# radiationsensor_r1.net
KiCad netlist of a schematic drawn in EAGLE
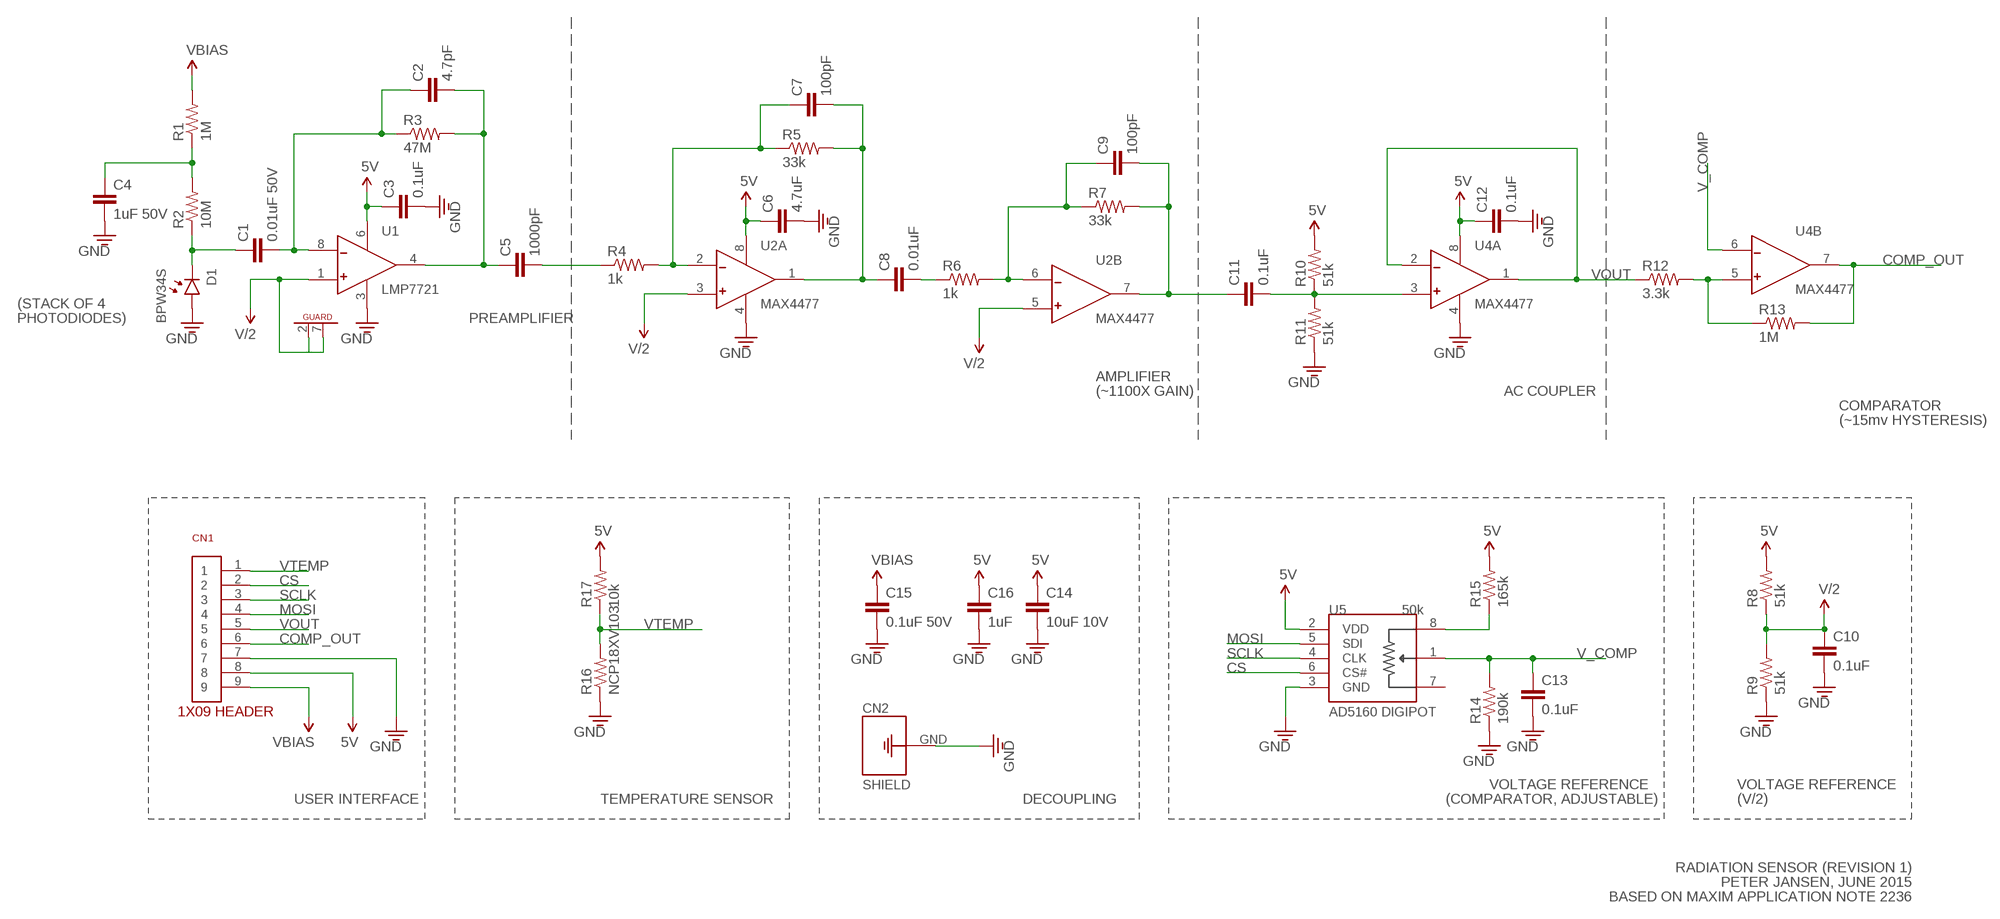
[diagram p0: schematic, sheet 1]

(export (version "E")
  (design (tool "Eeschema 10.0.6"))
  (components
    (comp (ref "C1")
      (value "0.01uF 50V")
      (footprint "eagle-import:0603")
      (libsource (lib "eagle-import") (part "CAP0603"))
    )
    (comp (ref "C2")
      (value "4.7pF")
      (footprint "eagle-import:0603")
      (libsource (lib "eagle-import") (part "CAP0603"))
    )
    (comp (ref "C3")
      (value "0.1uF")
      (footprint "eagle-import:0603")
      (libsource (lib "eagle-import") (part "CAP0603"))
    )
    (comp (ref "C4")
      (value "1uF 50V")
      (footprint "eagle-import:0603")
      (libsource (lib "eagle-import") (part "CAP0603"))
    )
    (comp (ref "C5")
      (value "1000pF")
      (footprint "eagle-import:0603")
      (libsource (lib "eagle-import") (part "CAP0603"))
    )
    (comp (ref "C6")
      (value "4.7uF")
      (footprint "eagle-import:0603")
      (libsource (lib "eagle-import") (part "CAP0603"))
    )
    (comp (ref "C7")
      (value "100pF")
      (footprint "eagle-import:0603")
      (libsource (lib "eagle-import") (part "CAP0603"))
    )
    (comp (ref "C8")
      (value "0.01uF")
      (footprint "eagle-import:0603")
      (libsource (lib "eagle-import") (part "CAP0603"))
    )
    (comp (ref "C9")
      (value "100pF")
      (footprint "eagle-import:0603")
      (libsource (lib "eagle-import") (part "CAP0603"))
    )
    (comp (ref "C10")
      (value "0.1uF")
      (footprint "eagle-import:0603")
      (libsource (lib "eagle-import") (part "CAP0603"))
    )
    (comp (ref "C11")
      (value "0.1uF")
      (footprint "eagle-import:0603")
      (libsource (lib "eagle-import") (part "CAP0603"))
    )
    (comp (ref "C12")
      (value "0.1uF")
      (footprint "eagle-import:0603")
      (libsource (lib "eagle-import") (part "CAP0603"))
    )
    (comp (ref "C13")
      (value "0.1uF")
      (footprint "eagle-import:0603")
      (libsource (lib "eagle-import") (part "CAP0603"))
    )
    (comp (ref "C14")
      (value "10uF 10V")
      (footprint "eagle-import:0805")
      (libsource (lib "eagle-import") (part "CAP0805"))
    )
    (comp (ref "C15")
      (value "0.1uF 50V")
      (footprint "eagle-import:0603")
      (libsource (lib "eagle-import") (part "CAP0603"))
    )
    (comp (ref "C16")
      (value "1uF")
      (footprint "eagle-import:0603")
      (libsource (lib "eagle-import") (part "CAP0603"))
    )
    (comp (ref "CN1")
      (value "1X09")
      (footprint "eagle-import:1X09")
      (libsource (lib "eagle-import") (part "1X09"))
    )
    (comp (ref "CN2")
      (value "GROUND-PAD")
      (footprint "eagle-import:GROUND-PAD")
      (libsource (lib "eagle-import") (part "GROUND-PAD"))
    )
    (comp (ref "D1")
      (value "BPW34S")
      (footprint "eagle-import:BPW34S-4STACK-SIDEMOUNT")
      (libsource (lib "eagle-import") (part "PHOTODIODE4STACK-SIDEMOUNT"))
    )
    (comp (ref "R1")
      (value "1M")
      (footprint "eagle-import:0603")
      (libsource (lib "eagle-import") (part "RESISTOR0603"))
    )
    (comp (ref "R2")
      (value "10M")
      (footprint "eagle-import:0603")
      (libsource (lib "eagle-import") (part "RESISTOR0603"))
    )
    (comp (ref "R3")
      (value "47M")
      (footprint "eagle-import:0603")
      (libsource (lib "eagle-import") (part "RESISTOR0603"))
    )
    (comp (ref "R4")
      (value "1k")
      (footprint "eagle-import:0603")
      (libsource (lib "eagle-import") (part "RESISTOR0603"))
    )
    (comp (ref "R5")
      (value "33k")
      (footprint "eagle-import:0603")
      (libsource (lib "eagle-import") (part "RESISTOR0603"))
    )
    (comp (ref "R6")
      (value "1k")
      (footprint "eagle-import:0603")
      (libsource (lib "eagle-import") (part "RESISTOR0603"))
    )
    (comp (ref "R7")
      (value "33k")
      (footprint "eagle-import:0603")
      (libsource (lib "eagle-import") (part "RESISTOR0603"))
    )
    (comp (ref "R8")
      (value "51k")
      (footprint "eagle-import:0603")
      (libsource (lib "eagle-import") (part "RESISTOR0603"))
    )
    (comp (ref "R9")
      (value "51k")
      (footprint "eagle-import:0603")
      (libsource (lib "eagle-import") (part "RESISTOR0603"))
    )
    (comp (ref "R10")
      (value "51k")
      (footprint "eagle-import:0603")
      (libsource (lib "eagle-import") (part "RESISTOR0603"))
    )
    (comp (ref "R11")
      (value "51k")
      (footprint "eagle-import:0603")
      (libsource (lib "eagle-import") (part "RESISTOR0603"))
    )
    (comp (ref "R12")
      (value "3.3k")
      (footprint "eagle-import:0603")
      (libsource (lib "eagle-import") (part "RESISTOR0603"))
    )
    (comp (ref "R13")
      (value "1M")
      (footprint "eagle-import:0603")
      (libsource (lib "eagle-import") (part "RESISTOR0603"))
    )
    (comp (ref "R14")
      (value "190k")
      (footprint "eagle-import:0603")
      (libsource (lib "eagle-import") (part "RESISTOR0603"))
    )
    (comp (ref "R15")
      (value "165k")
      (footprint "eagle-import:0603")
      (libsource (lib "eagle-import") (part "RESISTOR0603"))
    )
    (comp (ref "R16")
      (value "NCP18XV103")
      (footprint "eagle-import:0603")
      (libsource (lib "eagle-import") (part "RESISTOR0603"))
    )
    (comp (ref "R17")
      (value "10k")
      (footprint "eagle-import:0603")
      (libsource (lib "eagle-import") (part "RESISTOR0603"))
    )
    (comp (ref "U1")
      (value "LMP7721")
      (footprint "eagle-import:SOIC-8")
      (libsource (lib "eagle-import") (part "OPAMP-LMP7721"))
    )
    (comp (ref "U2")
      (value "MAX4477")
      (footprint "eagle-import:SOIC-8")
      (libsource (lib "eagle-import") (part "OPAMP-MAX4477"))
    )
    (comp (ref "U4")
      (value "MAX4477")
      (footprint "eagle-import:SOIC-8")
      (libsource (lib "eagle-import") (part "OPAMP-MAX4477"))
    )
    (comp (ref "U5")
      (value "50k")
      (footprint "eagle-import:SOT-23-8")
      (libsource (lib "eagle-import") (part "AD5160"))
    )
  )
  (nets
    (net (code "1") (name "/COMP_OUT") (class "Default")
      (node (ref "CN1") (pin "6") (pinfunction "6_6") (pintype "bidirectional"))
      (node (ref "R13") (pin "2") (pinfunction "2_2") (pintype "passive"))
      (node (ref "U4") (pin "7") (pinfunction "OUT_7") (pintype "bidirectional"))
    )
    (net (code "2") (name "/CS") (class "Default")
      (node (ref "CN1") (pin "2") (pinfunction "2_2") (pintype "bidirectional"))
      (node (ref "U5") (pin "6") (pinfunction "CS#_6") (pintype "bidirectional"))
    )
    (net (code "3") (name "/MOSI") (class "Default")
      (node (ref "CN1") (pin "4") (pinfunction "4_4") (pintype "bidirectional"))
      (node (ref "U5") (pin "5") (pinfunction "SDI_5") (pintype "bidirectional"))
    )
    (net (code "4") (name "/SCLK") (class "Default")
      (node (ref "CN1") (pin "3") (pinfunction "3_3") (pintype "bidirectional"))
      (node (ref "U5") (pin "4") (pinfunction "CLK_4") (pintype "bidirectional"))
    )
    (net (code "5") (name "/VOUT") (class "Default")
      (node (ref "CN1") (pin "5") (pinfunction "5_5") (pintype "bidirectional"))
      (node (ref "R12") (pin "1") (pinfunction "1_1") (pintype "passive"))
      (node (ref "U4") (pin "1") (pinfunction "OUT_1") (pintype "bidirectional"))
      (node (ref "U4") (pin "2") (pinfunction "-_2") (pintype "bidirectional"))
    )
    (net (code "6") (name "/VTEMP") (class "Default")
      (node (ref "CN1") (pin "1") (pinfunction "1_1") (pintype "bidirectional"))
      (node (ref "R16") (pin "2") (pinfunction "2_2") (pintype "passive"))
      (node (ref "R17") (pin "1") (pinfunction "1_1") (pintype "passive"))
    )
    (net (code "7") (name "/V_COMP") (class "Default")
      (node (ref "C13") (pin "1") (pinfunction "1_1") (pintype "passive"))
      (node (ref "R14") (pin "2") (pinfunction "2_2") (pintype "passive"))
      (node (ref "U4") (pin "6") (pinfunction "-_6") (pintype "bidirectional"))
      (node (ref "U5") (pin "1") (pinfunction "W_1") (pintype "bidirectional"))
    )
    (net (code "8") (name "5V") (class "Default")
      (node (ref "C12") (pin "1") (pinfunction "1_1") (pintype "passive"))
      (node (ref "C14") (pin "1") (pinfunction "1_1") (pintype "passive"))
      (node (ref "C16") (pin "1") (pinfunction "1_1") (pintype "passive"))
      (node (ref "C3") (pin "1") (pinfunction "1_1") (pintype "passive"))
      (node (ref "C6") (pin "1") (pinfunction "1_1") (pintype "passive"))
      (node (ref "CN1") (pin "8") (pinfunction "8_8") (pintype "bidirectional"))
      (node (ref "R10") (pin "2") (pinfunction "2_2") (pintype "passive"))
      (node (ref "R15") (pin "2") (pinfunction "2_2") (pintype "passive"))
      (node (ref "R17") (pin "2") (pinfunction "2_2") (pintype "passive"))
      (node (ref "R8") (pin "2") (pinfunction "2_2") (pintype "passive"))
      (node (ref "U1") (pin "6") (pinfunction "VCC_6") (pintype "bidirectional"))
      (node (ref "U2") (pin "8") (pinfunction "V+_8") (pintype "bidirectional"))
      (node (ref "U4") (pin "8") (pinfunction "V+_8") (pintype "bidirectional"))
      (node (ref "U5") (pin "2") (pinfunction "VDD_2") (pintype "bidirectional"))
    )
    (net (code "9") (name "GND") (class "Default")
      (node (ref "C10") (pin "2") (pinfunction "2_2") (pintype "passive"))
      (node (ref "C12") (pin "2") (pinfunction "2_2") (pintype "passive"))
      (node (ref "C13") (pin "2") (pinfunction "2_2") (pintype "passive"))
      (node (ref "C14") (pin "2") (pinfunction "2_2") (pintype "passive"))
      (node (ref "C15") (pin "2") (pinfunction "2_2") (pintype "passive"))
      (node (ref "C16") (pin "2") (pinfunction "2_2") (pintype "passive"))
      (node (ref "C3") (pin "2") (pinfunction "2_2") (pintype "passive"))
      (node (ref "C4") (pin "2") (pinfunction "2_2") (pintype "passive"))
      (node (ref "C6") (pin "2") (pinfunction "2_2") (pintype "passive"))
      (node (ref "CN1") (pin "7") (pinfunction "7_7") (pintype "bidirectional"))
      (node (ref "CN2") (pin "GND") (pinfunction "1_GND") (pintype "bidirectional"))
      (node (ref "D1") (pin "A") (pinfunction "ANODE_A") (pintype "bidirectional"))
      (node (ref "R11") (pin "1") (pinfunction "1_1") (pintype "passive"))
      (node (ref "R14") (pin "1") (pinfunction "1_1") (pintype "passive"))
      (node (ref "R16") (pin "1") (pinfunction "1_1") (pintype "passive"))
      (node (ref "R9") (pin "1") (pinfunction "1_1") (pintype "passive"))
      (node (ref "U1") (pin "3") (pinfunction "GND_3") (pintype "bidirectional"))
      (node (ref "U2") (pin "4") (pinfunction "V-_4") (pintype "bidirectional"))
      (node (ref "U4") (pin "4") (pinfunction "V-_4") (pintype "bidirectional"))
      (node (ref "U5") (pin "3") (pinfunction "GND_3") (pintype "bidirectional"))
    )
    (net (code "10") (name "Net-(C4-Pad1)") (class "Default")
      (node (ref "C4") (pin "1") (pinfunction "1_1") (pintype "passive"))
      (node (ref "R1") (pin "1") (pinfunction "1_1") (pintype "passive"))
      (node (ref "R2") (pin "2") (pinfunction "2_2") (pintype "passive"))
    )
    (net (code "11") (name "Net-(C5-Pad2)") (class "Default")
      (node (ref "C5") (pin "2") (pinfunction "2_2") (pintype "passive"))
      (node (ref "R4") (pin "1") (pinfunction "1_1") (pintype "passive"))
    )
    (net (code "12") (name "Net-(C8-Pad2)") (class "Default")
      (node (ref "C8") (pin "2") (pinfunction "2_2") (pintype "passive"))
      (node (ref "R6") (pin "1") (pinfunction "1_1") (pintype "passive"))
    )
    (net (code "13") (name "Net-(D1-CATHODE)") (class "Default")
      (node (ref "C1") (pin "1") (pinfunction "1_1") (pintype "passive"))
      (node (ref "D1") (pin "C") (pinfunction "CATHODE_C") (pintype "bidirectional"))
      (node (ref "R2") (pin "1") (pinfunction "1_1") (pintype "passive"))
    )
    (net (code "14") (name "Net-(U1--)") (class "Default")
      (node (ref "C1") (pin "2") (pinfunction "2_2") (pintype "passive"))
      (node (ref "C2") (pin "1") (pinfunction "1_1") (pintype "passive"))
      (node (ref "R3") (pin "1") (pinfunction "1_1") (pintype "passive"))
      (node (ref "U1") (pin "8") (pinfunction "-_8") (pintype "bidirectional"))
    )
    (net (code "15") (name "Net-(U1-OUT)") (class "Default")
      (node (ref "C2") (pin "2") (pinfunction "2_2") (pintype "passive"))
      (node (ref "C5") (pin "1") (pinfunction "1_1") (pintype "passive"))
      (node (ref "R3") (pin "2") (pinfunction "2_2") (pintype "passive"))
      (node (ref "U1") (pin "4") (pinfunction "OUT_4") (pintype "bidirectional"))
    )
    (net (code "16") (name "Net-(U2A--)") (class "Default")
      (node (ref "C7") (pin "1") (pinfunction "1_1") (pintype "passive"))
      (node (ref "R4") (pin "2") (pinfunction "2_2") (pintype "passive"))
      (node (ref "R5") (pin "1") (pinfunction "1_1") (pintype "passive"))
      (node (ref "U2") (pin "2") (pinfunction "-_2") (pintype "bidirectional"))
    )
    (net (code "17") (name "Net-(U2A-OUT)") (class "Default")
      (node (ref "C7") (pin "2") (pinfunction "2_2") (pintype "passive"))
      (node (ref "C8") (pin "1") (pinfunction "1_1") (pintype "passive"))
      (node (ref "R5") (pin "2") (pinfunction "2_2") (pintype "passive"))
      (node (ref "U2") (pin "1") (pinfunction "OUT_1") (pintype "bidirectional"))
    )
    (net (code "18") (name "Net-(U2B--)") (class "Default")
      (node (ref "C9") (pin "1") (pinfunction "1_1") (pintype "passive"))
      (node (ref "R6") (pin "2") (pinfunction "2_2") (pintype "passive"))
      (node (ref "R7") (pin "1") (pinfunction "1_1") (pintype "passive"))
      (node (ref "U2") (pin "6") (pinfunction "-_6") (pintype "bidirectional"))
    )
    (net (code "19") (name "Net-(U2B-OUT)") (class "Default")
      (node (ref "C11") (pin "1") (pinfunction "1_1") (pintype "passive"))
      (node (ref "C9") (pin "2") (pinfunction "2_2") (pintype "passive"))
      (node (ref "R7") (pin "2") (pinfunction "2_2") (pintype "passive"))
      (node (ref "U2") (pin "7") (pinfunction "OUT_7") (pintype "bidirectional"))
    )
    (net (code "20") (name "Net-(U4A-+)") (class "Default")
      (node (ref "C11") (pin "2") (pinfunction "2_2") (pintype "passive"))
      (node (ref "R10") (pin "1") (pinfunction "1_1") (pintype "passive"))
      (node (ref "R11") (pin "2") (pinfunction "2_2") (pintype "passive"))
      (node (ref "U4") (pin "3") (pinfunction "+_3") (pintype "bidirectional"))
    )
    (net (code "21") (name "Net-(U4B-+)") (class "Default")
      (node (ref "R12") (pin "2") (pinfunction "2_2") (pintype "passive"))
      (node (ref "R13") (pin "1") (pinfunction "1_1") (pintype "passive"))
      (node (ref "U4") (pin "5") (pinfunction "+_5") (pintype "bidirectional"))
    )
    (net (code "22") (name "Net-(U5-A)") (class "Default")
      (node (ref "R15") (pin "1") (pinfunction "1_1") (pintype "passive"))
      (node (ref "U5") (pin "8") (pinfunction "A_8") (pintype "bidirectional"))
    )
    (net (code "23") (name "VBIAS") (class "Default")
      (node (ref "C15") (pin "1") (pinfunction "1_1") (pintype "passive"))
      (node (ref "CN1") (pin "9") (pinfunction "9_9") (pintype "bidirectional"))
      (node (ref "R1") (pin "2") (pinfunction "2_2") (pintype "passive"))
    )
    (net (code "24") (name "V{slash}2") (class "Default")
      (node (ref "C10") (pin "1") (pinfunction "1_1") (pintype "passive"))
      (node (ref "R8") (pin "1") (pinfunction "1_1") (pintype "passive"))
      (node (ref "R9") (pin "2") (pinfunction "2_2") (pintype "passive"))
      (node (ref "U1") (pin "1") (pinfunction "+_1") (pintype "bidirectional"))
      (node (ref "U1") (pin "2") (pinfunction "G1_2") (pintype "bidirectional"))
      (node (ref "U1") (pin "7") (pinfunction "G2_7") (pintype "bidirectional"))
      (node (ref "U2") (pin "3") (pinfunction "+_3") (pintype "bidirectional"))
      (node (ref "U2") (pin "5") (pinfunction "+_5") (pintype "bidirectional"))
    )
    (net (code "25") (name "unconnected-(U5-B-Pad7)") (class "Default")
      (node (ref "U5") (pin "7") (pinfunction "B_7") (pintype "bidirectional"))
    )
  )
)
